# motorDriver.net
KiCad netlist of a schematic drawn in EAGLE
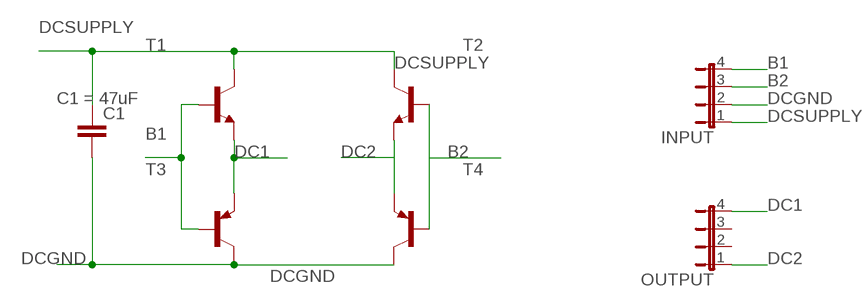
[diagram p0: schematic, sheet 1]

(export (version "E")
  (design (tool "Eeschema 10.0.6"))
  (components
    (comp (ref "C1")
      (value "C5/3.5")
      (footprint "eagle-import:C5B3.5")
      (fields (field (name "C1") "47uF"))
      (libsource (lib "eagle-import") (part "C5/3.5"))
    )
    (comp (ref "INPUT")
      (value "JP4E")
      (footprint "eagle-import:JP4")
      (libsource (lib "eagle-import") (part "JP4E"))
    )
    (comp (ref "OUTPUT")
      (value "JP4E")
      (footprint "eagle-import:JP4")
      (libsource (lib "eagle-import") (part "JP4E"))
    )
    (comp (ref "T1")
      (value "-NPN-SOT93V")
      (footprint "eagle-import:SOT93V")
      (libsource (lib "eagle-import") (part "-NPN-SOT93V"))
    )
    (comp (ref "T2")
      (value "-NPN-SOT93V")
      (footprint "eagle-import:SOT93V")
      (libsource (lib "eagle-import") (part "-NPN-SOT93V"))
    )
    (comp (ref "T3")
      (value "-PNP-SOT93V")
      (footprint "eagle-import:SOT93V")
      (libsource (lib "eagle-import") (part "-PNP-SOT93V"))
    )
    (comp (ref "T4")
      (value "-PNP-SOT93V")
      (footprint "eagle-import:SOT93V")
      (libsource (lib "eagle-import") (part "-PNP-SOT93V"))
    )
  )
  (nets
    (net (code "1") (name "/B1") (class "Default")
      (node (ref "INPUT") (pin "4") (pinfunction "4_4") (pintype "passive"))
      (node (ref "T1") (pin "B") (pinfunction "B_B") (pintype "passive"))
      (node (ref "T3") (pin "B") (pinfunction "B_B") (pintype "passive"))
    )
    (net (code "2") (name "/B2") (class "Default")
      (node (ref "INPUT") (pin "3") (pinfunction "3_3") (pintype "passive"))
      (node (ref "T2") (pin "B") (pinfunction "B_B") (pintype "passive"))
      (node (ref "T4") (pin "B") (pinfunction "B_B") (pintype "passive"))
    )
    (net (code "3") (name "/DC1") (class "Default")
      (node (ref "OUTPUT") (pin "4") (pinfunction "4_4") (pintype "passive"))
      (node (ref "T1") (pin "E") (pinfunction "E_E") (pintype "passive"))
      (node (ref "T3") (pin "E") (pinfunction "E_E") (pintype "passive"))
    )
    (net (code "4") (name "/DC2") (class "Default")
      (node (ref "OUTPUT") (pin "1") (pinfunction "1_1") (pintype "passive"))
      (node (ref "T2") (pin "E") (pinfunction "E_E") (pintype "passive"))
      (node (ref "T4") (pin "E") (pinfunction "E_E") (pintype "passive"))
    )
    (net (code "5") (name "/DCGND") (class "Default")
      (node (ref "C1") (pin "2") (pinfunction "2_2") (pintype "passive"))
      (node (ref "INPUT") (pin "2") (pinfunction "2_2") (pintype "passive"))
      (node (ref "T3") (pin "C") (pinfunction "C_C") (pintype "passive"))
      (node (ref "T4") (pin "C") (pinfunction "C_C") (pintype "passive"))
    )
    (net (code "6") (name "/DCSUPPLY") (class "Default")
      (node (ref "C1") (pin "1") (pinfunction "1_1") (pintype "passive"))
      (node (ref "INPUT") (pin "1") (pinfunction "1_1") (pintype "passive"))
      (node (ref "T1") (pin "C") (pinfunction "C_C") (pintype "passive"))
      (node (ref "T2") (pin "C") (pinfunction "C_C") (pintype "passive"))
    )
    (net (code "7") (name "unconnected-(OUTPUT-Pad2)") (class "Default")
      (node (ref "OUTPUT") (pin "2") (pinfunction "2_2") (pintype "passive"))
    )
    (net (code "8") (name "unconnected-(OUTPUT-Pad3)") (class "Default")
      (node (ref "OUTPUT") (pin "3") (pinfunction "3_3") (pintype "passive"))
    )
  )
)
